# VCA-3080_io.net
KiCad netlist of a schematic drawn in EAGLE
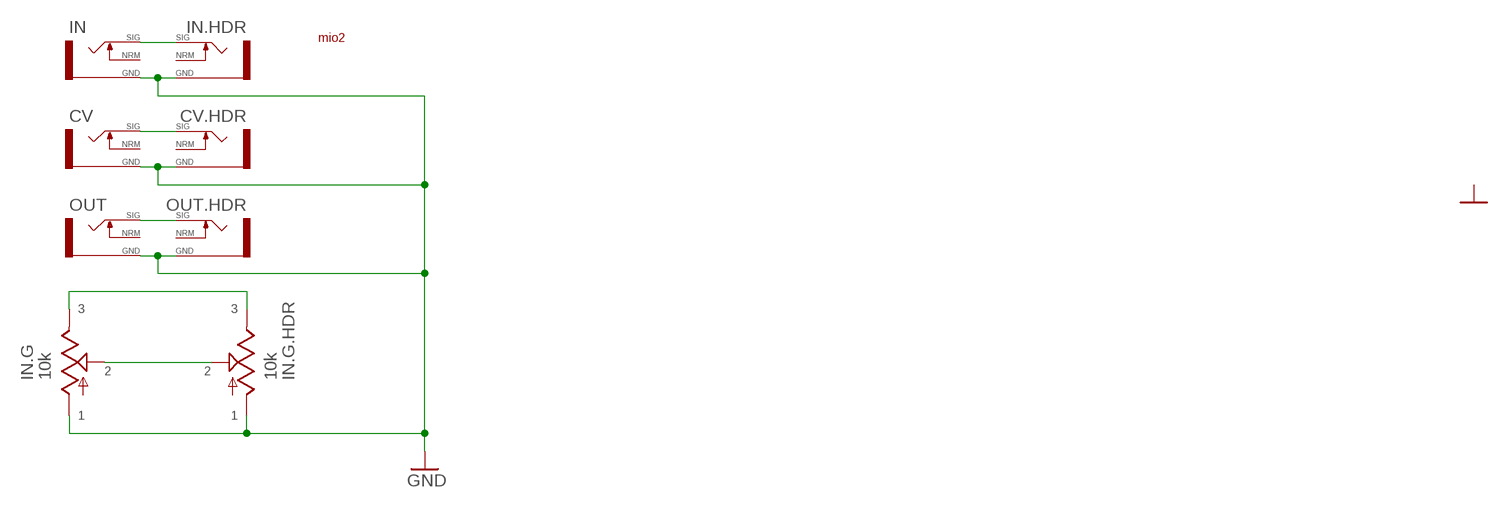
[diagram p0: schematic, sheet 1]

(export (version "E")
  (design (tool "Eeschema 10.0.6"))
  (components
    (comp (ref "CV")
      (value "MONO301M")
      (footprint "eagle-import:PJ301M")
      (libsource (lib "eagle-import") (part "MONO301M"))
    )
    (comp (ref "CV.HDR")
      (value "MONOHDR")
      (footprint "eagle-import:HEADER")
      (libsource (lib "eagle-import") (part "MONOHDR"))
    )
    (comp (ref "IN")
      (value "MONO301M")
      (footprint "eagle-import:PJ301M")
      (libsource (lib "eagle-import") (part "MONO301M"))
    )
    (comp (ref "IN.G")
      (value "10k")
      (footprint "eagle-import:ALPHA-VERT")
      (libsource (lib "eagle-import") (part "PALPHA"))
    )
    (comp (ref "IN.G.HDR")
      (value "10k")
      (footprint "eagle-import:HEADER")
      (libsource (lib "eagle-import") (part "PHDR"))
    )
    (comp (ref "IN.HDR")
      (value "MONOHDR")
      (footprint "eagle-import:HEADER")
      (libsource (lib "eagle-import") (part "MONOHDR"))
    )
    (comp (ref "OUT")
      (value "MONO301M")
      (footprint "eagle-import:PJ301M")
      (libsource (lib "eagle-import") (part "MONO301M"))
    )
    (comp (ref "OUT.HDR")
      (value "MONOHDR")
      (footprint "eagle-import:HEADER")
      (libsource (lib "eagle-import") (part "MONOHDR"))
    )
    (comp (ref "U$2")
      (value "MIO2")
      (footprint "eagle-import:MIO2")
      (libsource (lib "eagle-import") (part "MIO2"))
    )
  )
  (nets
    (net (code "1") (name "GND") (class "Default")
      (node (ref "CV") (pin "SLV") (pinfunction "SLEEVE-GND_SLV") (pintype "passive"))
      (node (ref "CV.HDR") (pin "GND") (pinfunction "SLEEVE-GND_GND") (pintype "passive"))
      (node (ref "IN") (pin "SLV") (pinfunction "SLEEVE-GND_SLV") (pintype "passive"))
      (node (ref "IN.G") (pin "1") (pinfunction "1_1") (pintype "passive"))
      (node (ref "IN.G.HDR") (pin "1") (pinfunction "1_1") (pintype "passive"))
      (node (ref "IN.HDR") (pin "GND") (pinfunction "SLEEVE-GND_GND") (pintype "passive"))
      (node (ref "OUT") (pin "SLV") (pinfunction "SLEEVE-GND_SLV") (pintype "passive"))
      (node (ref "OUT.HDR") (pin "GND") (pinfunction "SLEEVE-GND_GND") (pintype "passive"))
    )
    (net (code "2") (name "Net-(CV-TIP-SIG)") (class "Default")
      (node (ref "CV") (pin "TIP") (pinfunction "TIP-SIG_TIP") (pintype "passive"))
      (node (ref "CV.HDR") (pin "TIP-SIG") (pinfunction "TIP-SIG_TIP-SIG") (pintype "passive"))
    )
    (net (code "3") (name "Net-(IN-TIP-SIG)") (class "Default")
      (node (ref "IN") (pin "TIP") (pinfunction "TIP-SIG_TIP") (pintype "passive"))
      (node (ref "IN.HDR") (pin "TIP-SIG") (pinfunction "TIP-SIG_TIP-SIG") (pintype "passive"))
    )
    (net (code "4") (name "Net-(IN.G-Pad2)") (class "Default")
      (node (ref "IN.G") (pin "2") (pinfunction "2_2") (pintype "passive"))
      (node (ref "IN.G.HDR") (pin "2") (pinfunction "2_2") (pintype "passive"))
    )
    (net (code "5") (name "Net-(IN.G-Pad3)") (class "Default")
      (node (ref "IN.G") (pin "3") (pinfunction "3_3") (pintype "passive"))
      (node (ref "IN.G.HDR") (pin "3") (pinfunction "3_3") (pintype "passive"))
    )
    (net (code "6") (name "Net-(OUT-TIP-SIG)") (class "Default")
      (node (ref "OUT") (pin "TIP") (pinfunction "TIP-SIG_TIP") (pintype "passive"))
      (node (ref "OUT.HDR") (pin "TIP-SIG") (pinfunction "TIP-SIG_TIP-SIG") (pintype "passive"))
    )
    (net (code "7") (name "unconnected-(CV-SWITCH-NORM-PadSW)") (class "Default")
      (node (ref "CV") (pin "SW") (pinfunction "SWITCH-NORM_SW") (pintype "passive"))
    )
    (net (code "8") (name "unconnected-(CV.HDR-SWITCH-NORM-PadNORM)") (class "Default")
      (node (ref "CV.HDR") (pin "NORM") (pinfunction "SWITCH-NORM_NORM") (pintype "passive"))
    )
    (net (code "9") (name "unconnected-(IN-SWITCH-NORM-PadSW)") (class "Default")
      (node (ref "IN") (pin "SW") (pinfunction "SWITCH-NORM_SW") (pintype "passive"))
    )
    (net (code "10") (name "unconnected-(IN.HDR-SWITCH-NORM-PadNORM)") (class "Default")
      (node (ref "IN.HDR") (pin "NORM") (pinfunction "SWITCH-NORM_NORM") (pintype "passive"))
    )
    (net (code "11") (name "unconnected-(OUT-SWITCH-NORM-PadSW)") (class "Default")
      (node (ref "OUT") (pin "SW") (pinfunction "SWITCH-NORM_SW") (pintype "passive"))
    )
    (net (code "12") (name "unconnected-(OUT.HDR-SWITCH-NORM-PadNORM)") (class "Default")
      (node (ref "OUT.HDR") (pin "NORM") (pinfunction "SWITCH-NORM_NORM") (pintype "passive"))
    )
  )
)
